# DPPXHK_10CL010_POWER.net
KiCad netlist of a schematic drawn in Altium Designer
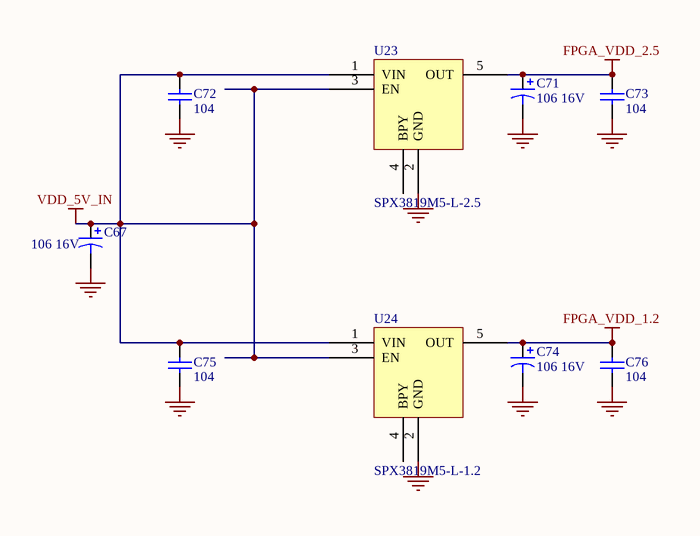
[diagram p0: DPPXHK_10CL010_POWER.SchDoc]

(export (version "E")
  (design (tool "Eeschema 10.0.6"))
  (components
    (comp (ref "C67")
      (value "106 16V")
      (footprint "LC0402")
      (description "Polarized Capacitor (Surface Mount)")
      (fields (field (name "PUBLISHER") "Altium Limited"))
      (libsource (lib "Miscellaneous Devices") (part "Cap Pol3"))
    )
    (comp (ref "C71")
      (value "106 16V")
      (footprint "LC0402")
      (description "Polarized Capacitor (Surface Mount)")
      (fields (field (name "PUBLISHER") "Altium Limited"))
      (libsource (lib "Miscellaneous Devices") (part "Cap Pol3"))
    )
    (comp (ref "C72")
      (value "104")
      (footprint "LC0402")
      (description "Capacitor (Semiconductor SIM Model)")
      (fields (field (name "PUBLISHER") "Altium Limited"))
      (libsource (lib "Miscellaneous Devices") (part "Cap Semi"))
    )
    (comp (ref "C73")
      (value "104")
      (footprint "LC0402")
      (description "Capacitor (Semiconductor SIM Model)")
      (fields (field (name "PUBLISHER") "Altium Limited"))
      (libsource (lib "Miscellaneous Devices") (part "Cap Semi"))
    )
    (comp (ref "C74")
      (value "106 16V")
      (footprint "LC0402")
      (description "Polarized Capacitor (Surface Mount)")
      (fields (field (name "PUBLISHER") "Altium Limited"))
      (libsource (lib "Miscellaneous Devices") (part "Cap Pol3"))
    )
    (comp (ref "C75")
      (value "104")
      (footprint "LC0402")
      (description "Capacitor (Semiconductor SIM Model)")
      (fields (field (name "PUBLISHER") "Altium Limited"))
      (libsource (lib "Miscellaneous Devices") (part "Cap Semi"))
    )
    (comp (ref "C76")
      (value "104")
      (footprint "LC0402")
      (description "Capacitor (Semiconductor SIM Model)")
      (fields (field (name "PUBLISHER") "Altium Limited"))
      (libsource (lib "Miscellaneous Devices") (part "Cap Semi"))
    )
    (comp (ref "U23")
      (value "SPX3819M5-L-2.5")
      (footprint "SOT-23-5")
      (libsource (lib "PXHK") (part "SPX3819"))
    )
    (comp (ref "U24")
      (value "SPX3819M5-L-1.2")
      (footprint "SOT-23-5")
      (libsource (lib "PXHK") (part "SPX3819"))
    )
  )
  (nets
    (net (code "1") (name "FPGA_VDD_1.2") (class "Default")
      (node (ref "C74") (pin "1") (pinfunction "1_1") (pintype "passive"))
      (node (ref "C76") (pin "2") (pinfunction "2_2") (pintype "passive"))
      (node (ref "U24") (pin "5") (pinfunction "OUT_5") (pintype "passive"))
    )
    (net (code "2") (name "FPGA_VDD_2.5") (class "Default")
      (node (ref "C71") (pin "1") (pinfunction "1_1") (pintype "passive"))
      (node (ref "C73") (pin "2") (pinfunction "2_2") (pintype "passive"))
      (node (ref "U23") (pin "5") (pinfunction "OUT_5") (pintype "passive"))
    )
    (net (code "3") (name "GND") (class "Default")
      (node (ref "C67") (pin "2") (pinfunction "2_2") (pintype "passive"))
      (node (ref "C71") (pin "2") (pinfunction "2_2") (pintype "passive"))
      (node (ref "C72") (pin "1") (pinfunction "1_1") (pintype "passive"))
      (node (ref "C73") (pin "1") (pinfunction "1_1") (pintype "passive"))
      (node (ref "C74") (pin "2") (pinfunction "2_2") (pintype "passive"))
      (node (ref "C75") (pin "1") (pinfunction "1_1") (pintype "passive"))
      (node (ref "C76") (pin "1") (pinfunction "1_1") (pintype "passive"))
      (node (ref "U23") (pin "2") (pinfunction "GND_2") (pintype "passive"))
      (node (ref "U24") (pin "2") (pinfunction "GND_2") (pintype "passive"))
    )
    (net (code "4") (name "VDD_5V_IN") (class "Default")
      (node (ref "C67") (pin "1") (pinfunction "1_1") (pintype "passive"))
      (node (ref "C72") (pin "2") (pinfunction "2_2") (pintype "passive"))
      (node (ref "C75") (pin "2") (pinfunction "2_2") (pintype "passive"))
      (node (ref "U23") (pin "1") (pinfunction "VIN_1") (pintype "passive"))
      (node (ref "U23") (pin "3") (pinfunction "EN_3") (pintype "passive"))
      (node (ref "U24") (pin "1") (pinfunction "VIN_1") (pintype "passive"))
      (node (ref "U24") (pin "3") (pinfunction "EN_3") (pintype "passive"))
    )
    (net (code "5") (name "unconnected-(U23-BPY-Pad4)") (class "Default")
      (node (ref "U23") (pin "4") (pinfunction "BPY_4") (pintype "passive"))
    )
    (net (code "6") (name "unconnected-(U24-BPY-Pad4)") (class "Default")
      (node (ref "U24") (pin "4") (pinfunction "BPY_4") (pintype "passive"))
    )
  )
)
